# robot_booster.net
KiCad netlist of a schematic drawn in EAGLE
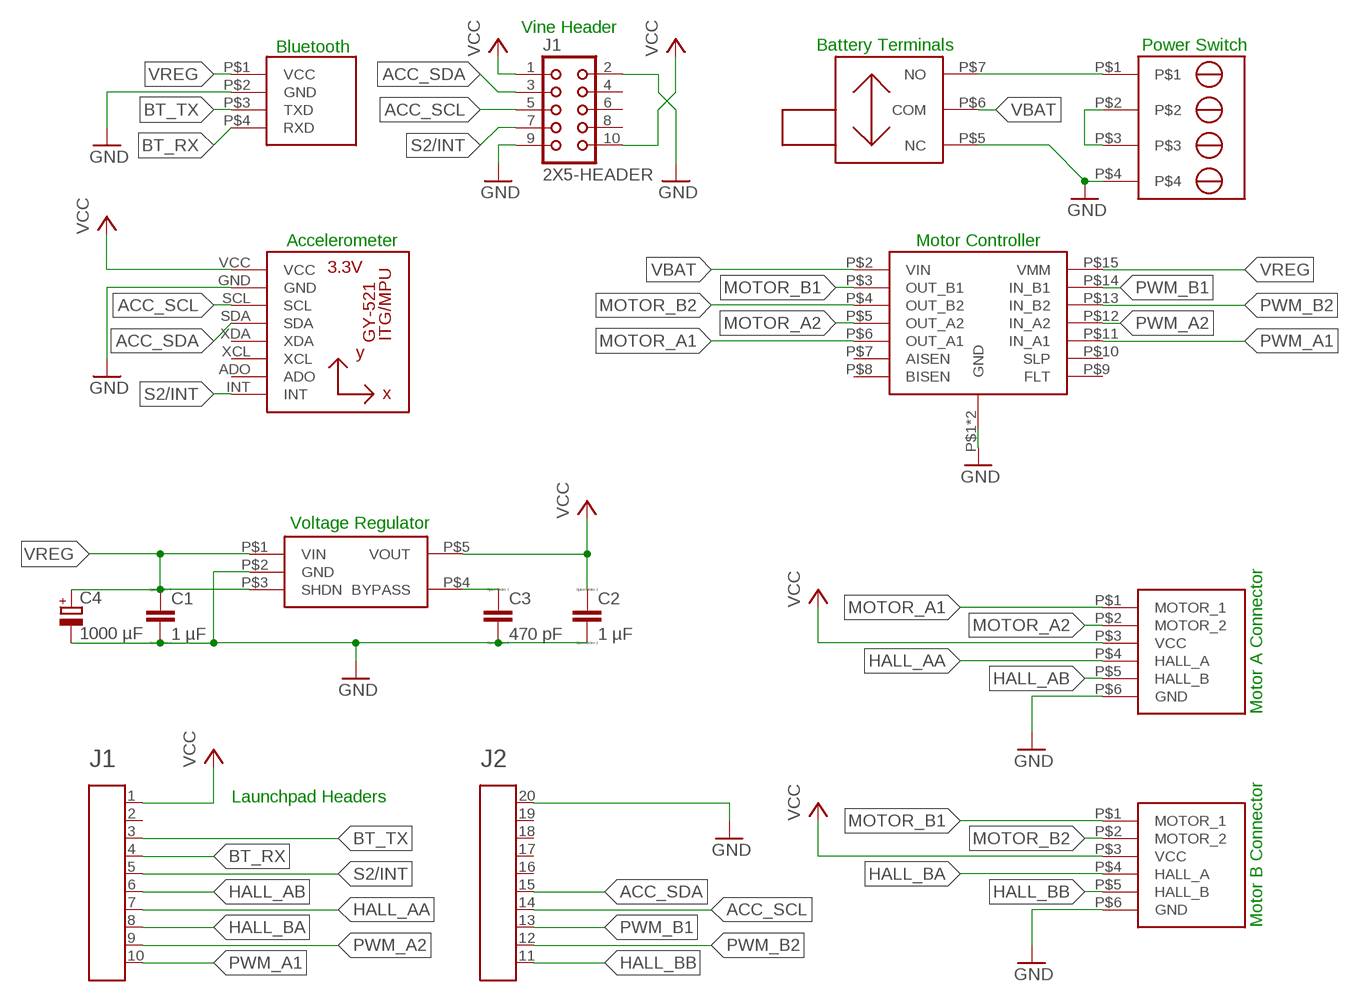
[diagram p0: schematic, sheet 1]

(export (version "E")
  (design (tool "Eeschema 10.0.6"))
  (components
    (comp (ref "C1")
      (value "1 µF")
      (footprint "eagle-import:C0603")
      (libsource (lib "eagle-import") (part "CC0603"))
    )
    (comp (ref "C2")
      (value "1 µF")
      (footprint "eagle-import:C0603")
      (libsource (lib "eagle-import") (part "CC0603"))
    )
    (comp (ref "C3")
      (value "470 pF")
      (footprint "eagle-import:C0603")
      (libsource (lib "eagle-import") (part "CC0603"))
    )
    (comp (ref "C4")
      (value "1000 µF")
      (footprint "eagle-import:E5-5")
      (libsource (lib "eagle-import") (part "CPOL-EUE5-5"))
    )
    (comp (ref "J1")
      (value "2X5-HEADER")
      (footprint "eagle-import:2X5_1.27MM_SMALL")
      (libsource (lib "eagle-import") (part "2X5-HEADER"))
    )
    (comp (ref "U$1")
      (value "HEADER2X10-BOOSTERPACK")
      (footprint "eagle-import:2X10-BOOSTERPACK")
      (libsource (lib "eagle-import") (part "HEADER2X10-BOOSTERPACK"))
    )
    (comp (ref "U$2")
      (value "POLOLU-MICROMETAL-ENCODER")
      (footprint "eagle-import:2MM-1X6-JST")
      (libsource (lib "eagle-import") (part "POLOLU-MICROMETAL-ENCODER"))
    )
    (comp (ref "U$3")
      (value "POLOLU-MICROMETAL-ENCODER")
      (footprint "eagle-import:2MM-1X6-JST")
      (libsource (lib "eagle-import") (part "POLOLU-MICROMETAL-ENCODER"))
    )
    (comp (ref "U$4")
      (value "POLOLU-DRV8833")
      (footprint "eagle-import:HEADER-2X8-4W")
      (libsource (lib "eagle-import") (part "POLOLU-DRV8833"))
    )
    (comp (ref "U$5")
      (value "TC1015")
      (footprint "eagle-import:5-PIN-SOT-23")
      (libsource (lib "eagle-import") (part "TC1015"))
    )
    (comp (ref "U$6")
      (value "HC06-RIGHT-ANGLE-HEADER")
      (footprint "eagle-import:HEADER-4X1-RIGHT-ANGLE")
      (libsource (lib "eagle-import") (part "HC06-RIGHT-ANGLE-HEADER"))
    )
    (comp (ref "U$7")
      (value "1X4-SCREW-TERMINAL-BLOCK-OSTTE040104")
      (footprint "eagle-import:1X04-SCREW-TERMINAL-BLOCK-OSTTE040104")
      (libsource (lib "eagle-import") (part "1X4-SCREW-TERMINAL-BLOCK-OSTTE040104"))
    )
    (comp (ref "U$8")
      (value "SWITCH-EG1224")
      (footprint "eagle-import:SWITCH-EG122-RIGHT-ANGLE")
      (libsource (lib "eagle-import") (part "SWITCH-EG1224"))
    )
    (comp (ref "U1")
      (value "GY-521-HEADER")
      (footprint "eagle-import:GY-521-HEADER")
      (libsource (lib "eagle-import") (part "GY-521-HEADER"))
    )
  )
  (nets
    (net (code "1") (name "ACC_SCL") (class "Default")
      (node (ref "J1") (pin "5") (pinfunction "5_5") (pintype "passive"))
      (node (ref "U$1") (pin "14") (pinfunction "P$14_14") (pintype "bidirectional"))
      (node (ref "U1") (pin "SCL") (pinfunction "SCL_SCL") (pintype "bidirectional"))
    )
    (net (code "2") (name "ACC_SDA") (class "Default")
      (node (ref "J1") (pin "3") (pinfunction "3_3") (pintype "passive"))
      (node (ref "U$1") (pin "15") (pinfunction "P$15_15") (pintype "bidirectional"))
      (node (ref "U1") (pin "SDA") (pinfunction "SDA_SDA") (pintype "bidirectional"))
    )
    (net (code "3") (name "BT_RX") (class "Default")
      (node (ref "U$1") (pin "4") (pinfunction "P$4_4") (pintype "bidirectional"))
      (node (ref "U$6") (pin "P$4") (pinfunction "RXD_P$4") (pintype "input"))
    )
    (net (code "4") (name "BT_TX") (class "Default")
      (node (ref "U$1") (pin "3") (pinfunction "P$3_3") (pintype "bidirectional"))
      (node (ref "U$6") (pin "P$3") (pinfunction "TXD_P$3") (pintype "output"))
    )
    (net (code "5") (name "GND") (class "Default")
      (node (ref "C1") (pin "2") (pinfunction "2_2") (pintype "passive"))
      (node (ref "C2") (pin "2") (pinfunction "2_2") (pintype "passive"))
      (node (ref "C3") (pin "2") (pinfunction "2_2") (pintype "passive"))
      (node (ref "C4") (pin "-") (pinfunction "-_-") (pintype "passive"))
      (node (ref "J1") (pin "2") (pinfunction "2_2") (pintype "passive"))
      (node (ref "J1") (pin "9") (pinfunction "9_9") (pintype "passive"))
      (node (ref "U$1") (pin "20") (pinfunction "P$20_20") (pintype "power_in"))
      (node (ref "U$2") (pin "P$6") (pinfunction "GND_P$6") (pintype "power_in"))
      (node (ref "U$3") (pin "P$6") (pinfunction "GND_P$6") (pintype "power_in"))
      (node (ref "U$4") (pin "P$1") (pinfunction "GND_P$1") (pintype "power_in"))
      (node (ref "U$4") (pin "P$16") (pinfunction "GND_P$16") (pintype "power_in"))
      (node (ref "U$5") (pin "P$2") (pinfunction "GND_P$2") (pintype "power_in"))
      (node (ref "U$6") (pin "P$2") (pinfunction "GND_P$2") (pintype "power_in"))
      (node (ref "U$7") (pin "P$4") (pinfunction "P$4_P$4") (pintype "bidirectional"))
      (node (ref "U$8") (pin "P$5") (pinfunction "NC_P$5") (pintype "bidirectional"))
      (node (ref "U1") (pin "GND") (pinfunction "GND_GND") (pintype "power_in"))
    )
    (net (code "6") (name "HALL_AA") (class "Default")
      (node (ref "U$1") (pin "7") (pinfunction "P$7_7") (pintype "bidirectional"))
      (node (ref "U$2") (pin "P$4") (pinfunction "HALL_A_P$4") (pintype "output"))
    )
    (net (code "7") (name "HALL_AB") (class "Default")
      (node (ref "U$1") (pin "6") (pinfunction "P$6_6") (pintype "bidirectional"))
      (node (ref "U$2") (pin "P$5") (pinfunction "HALL_B_P$5") (pintype "output"))
    )
    (net (code "8") (name "HALL_BA") (class "Default")
      (node (ref "U$1") (pin "8") (pinfunction "P$8_8") (pintype "bidirectional"))
      (node (ref "U$3") (pin "P$4") (pinfunction "HALL_A_P$4") (pintype "output"))
    )
    (net (code "9") (name "HALL_BB") (class "Default")
      (node (ref "U$1") (pin "11") (pinfunction "P$11_11") (pintype "bidirectional"))
      (node (ref "U$3") (pin "P$5") (pinfunction "HALL_B_P$5") (pintype "output"))
    )
    (net (code "10") (name "MOTOR_A1") (class "Default")
      (node (ref "U$2") (pin "P$1") (pinfunction "MOTOR_1_P$1") (pintype "input"))
      (node (ref "U$4") (pin "P$6") (pinfunction "OUT_A1_P$6") (pintype "output"))
    )
    (net (code "11") (name "MOTOR_A2") (class "Default")
      (node (ref "U$2") (pin "P$2") (pinfunction "MOTOR_2_P$2") (pintype "input"))
      (node (ref "U$4") (pin "P$5") (pinfunction "OUT_A2_P$5") (pintype "output"))
    )
    (net (code "12") (name "MOTOR_B1") (class "Default")
      (node (ref "U$3") (pin "P$1") (pinfunction "MOTOR_1_P$1") (pintype "input"))
      (node (ref "U$4") (pin "P$3") (pinfunction "OUT_B1_P$3") (pintype "output"))
    )
    (net (code "13") (name "MOTOR_B2") (class "Default")
      (node (ref "U$3") (pin "P$2") (pinfunction "MOTOR_2_P$2") (pintype "input"))
      (node (ref "U$4") (pin "P$4") (pinfunction "OUT_B2_P$4") (pintype "output"))
    )
    (net (code "14") (name "Net-(U$5-BYPASS)") (class "Default")
      (node (ref "C3") (pin "1") (pinfunction "1_1") (pintype "passive"))
      (node (ref "U$5") (pin "P$4") (pinfunction "BYPASS_P$4") (pintype "bidirectional"))
    )
    (net (code "15") (name "Net-(U$7-PadP$2)") (class "Default")
      (node (ref "U$7") (pin "P$2") (pinfunction "P$2_P$2") (pintype "bidirectional"))
      (node (ref "U$7") (pin "P$3") (pinfunction "P$3_P$3") (pintype "bidirectional"))
    )
    (net (code "16") (name "Net-(U$8-NO)") (class "Default")
      (node (ref "U$7") (pin "P$1") (pinfunction "P$1_P$1") (pintype "bidirectional"))
      (node (ref "U$8") (pin "P$7") (pinfunction "NO_P$7") (pintype "bidirectional"))
    )
    (net (code "17") (name "PWM_A1") (class "Default")
      (node (ref "U$1") (pin "10") (pinfunction "P$10_10") (pintype "bidirectional"))
      (node (ref "U$4") (pin "P$11") (pinfunction "IN_A1_P$11") (pintype "input"))
    )
    (net (code "18") (name "PWM_A2") (class "Default")
      (node (ref "U$1") (pin "9") (pinfunction "P$9_9") (pintype "bidirectional"))
      (node (ref "U$4") (pin "P$12") (pinfunction "IN_A2_P$12") (pintype "input"))
    )
    (net (code "19") (name "PWM_B1") (class "Default")
      (node (ref "U$1") (pin "13") (pinfunction "P$13_13") (pintype "bidirectional"))
      (node (ref "U$4") (pin "P$14") (pinfunction "IN_B1_P$14") (pintype "input"))
    )
    (net (code "20") (name "PWM_B2") (class "Default")
      (node (ref "U$1") (pin "12") (pinfunction "P$12_12") (pintype "bidirectional"))
      (node (ref "U$4") (pin "P$13") (pinfunction "IN_B2_P$13") (pintype "input"))
    )
    (net (code "21") (name "S2{slash}INT") (class "Default")
      (node (ref "J1") (pin "7") (pinfunction "7_7") (pintype "passive"))
      (node (ref "U$1") (pin "5") (pinfunction "P$5_5") (pintype "bidirectional"))
      (node (ref "U1") (pin "INT") (pinfunction "INT_INT") (pintype "bidirectional"))
    )
    (net (code "22") (name "VBAT") (class "Default")
      (node (ref "U$4") (pin "P$2") (pinfunction "VIN_P$2") (pintype "power_in"))
      (node (ref "U$8") (pin "P$6") (pinfunction "COM_P$6") (pintype "bidirectional"))
    )
    (net (code "23") (name "VCC") (class "Default")
      (node (ref "C2") (pin "1") (pinfunction "1_1") (pintype "passive"))
      (node (ref "J1") (pin "1") (pinfunction "1_1") (pintype "passive"))
      (node (ref "J1") (pin "10") (pinfunction "10_10") (pintype "passive"))
      (node (ref "U$1") (pin "1") (pinfunction "P$1_1") (pintype "power_in"))
      (node (ref "U$2") (pin "P$3") (pinfunction "VCC_P$3") (pintype "power_in"))
      (node (ref "U$3") (pin "P$3") (pinfunction "VCC_P$3") (pintype "power_in"))
      (node (ref "U$5") (pin "P$5") (pinfunction "VOUT_P$5") (pintype "power_in"))
      (node (ref "U1") (pin "VCC") (pinfunction "VCC_VCC") (pintype "power_in"))
    )
    (net (code "24") (name "VREG") (class "Default")
      (node (ref "C1") (pin "1") (pinfunction "1_1") (pintype "passive"))
      (node (ref "C4") (pin "+") (pinfunction "+_+") (pintype "passive"))
      (node (ref "U$4") (pin "P$15") (pinfunction "VMM_P$15") (pintype "power_in"))
      (node (ref "U$5") (pin "P$1") (pinfunction "VIN_P$1") (pintype "power_in"))
      (node (ref "U$5") (pin "P$3") (pinfunction "SHDN_P$3") (pintype "input"))
      (node (ref "U$6") (pin "P$1") (pinfunction "VCC_P$1") (pintype "power_in"))
    )
    (net (code "25") (name "unconnected-(J1-Pad4)") (class "Default")
      (node (ref "J1") (pin "4") (pinfunction "4_4") (pintype "passive"))
    )
    (net (code "26") (name "unconnected-(J1-Pad6)") (class "Default")
      (node (ref "J1") (pin "6") (pinfunction "6_6") (pintype "passive"))
    )
    (net (code "27") (name "unconnected-(J1-Pad8)") (class "Default")
      (node (ref "J1") (pin "8") (pinfunction "8_8") (pintype "passive"))
    )
    (net (code "28") (name "unconnected-(U$1-P$2-Pad2)") (class "Default")
      (node (ref "U$1") (pin "2") (pinfunction "P$2_2") (pintype "bidirectional"))
    )
    (net (code "29") (name "unconnected-(U$1-P$16-Pad16)") (class "Default")
      (node (ref "U$1") (pin "16") (pinfunction "P$16_16") (pintype "no_connect"))
    )
    (net (code "30") (name "unconnected-(U$1-P$17-Pad17)") (class "Default")
      (node (ref "U$1") (pin "17") (pinfunction "P$17_17") (pintype "no_connect"))
    )
    (net (code "31") (name "unconnected-(U$1-P$18-Pad18)") (class "Default")
      (node (ref "U$1") (pin "18") (pinfunction "P$18_18") (pintype "no_connect"))
    )
    (net (code "32") (name "unconnected-(U$1-P$19-Pad19)") (class "Default")
      (node (ref "U$1") (pin "19") (pinfunction "P$19_19") (pintype "no_connect"))
    )
    (net (code "33") (name "unconnected-(U$4-AISEN-PadP$7)") (class "Default")
      (node (ref "U$4") (pin "P$7") (pinfunction "AISEN_P$7") (pintype "input"))
    )
    (net (code "34") (name "unconnected-(U$4-BISEN-PadP$8)") (class "Default")
      (node (ref "U$4") (pin "P$8") (pinfunction "BISEN_P$8") (pintype "input"))
    )
    (net (code "35") (name "unconnected-(U$4-FLT-PadP$9)") (class "Default")
      (node (ref "U$4") (pin "P$9") (pinfunction "FLT_P$9") (pintype "output"))
    )
    (net (code "36") (name "unconnected-(U$4-SLP-PadP$10)") (class "Default")
      (node (ref "U$4") (pin "P$10") (pinfunction "SLP_P$10") (pintype "input"))
    )
    (net (code "37") (name "unconnected-(U1-PadADO)") (class "Default")
      (node (ref "U1") (pin "ADO") (pinfunction "ADO_ADO") (pintype "bidirectional"))
    )
    (net (code "38") (name "unconnected-(U1-PadXCL)") (class "Default")
      (node (ref "U1") (pin "XCL") (pinfunction "XCL_XCL") (pintype "bidirectional"))
    )
    (net (code "39") (name "unconnected-(U1-PadXDA)") (class "Default")
      (node (ref "U1") (pin "XDA") (pinfunction "XDA_XDA") (pintype "bidirectional"))
    )
  )
)
